# LB_BIT_i19_ROLLERSWITCH-v03_rev3.net
KiCad netlist of a schematic drawn in EAGLE
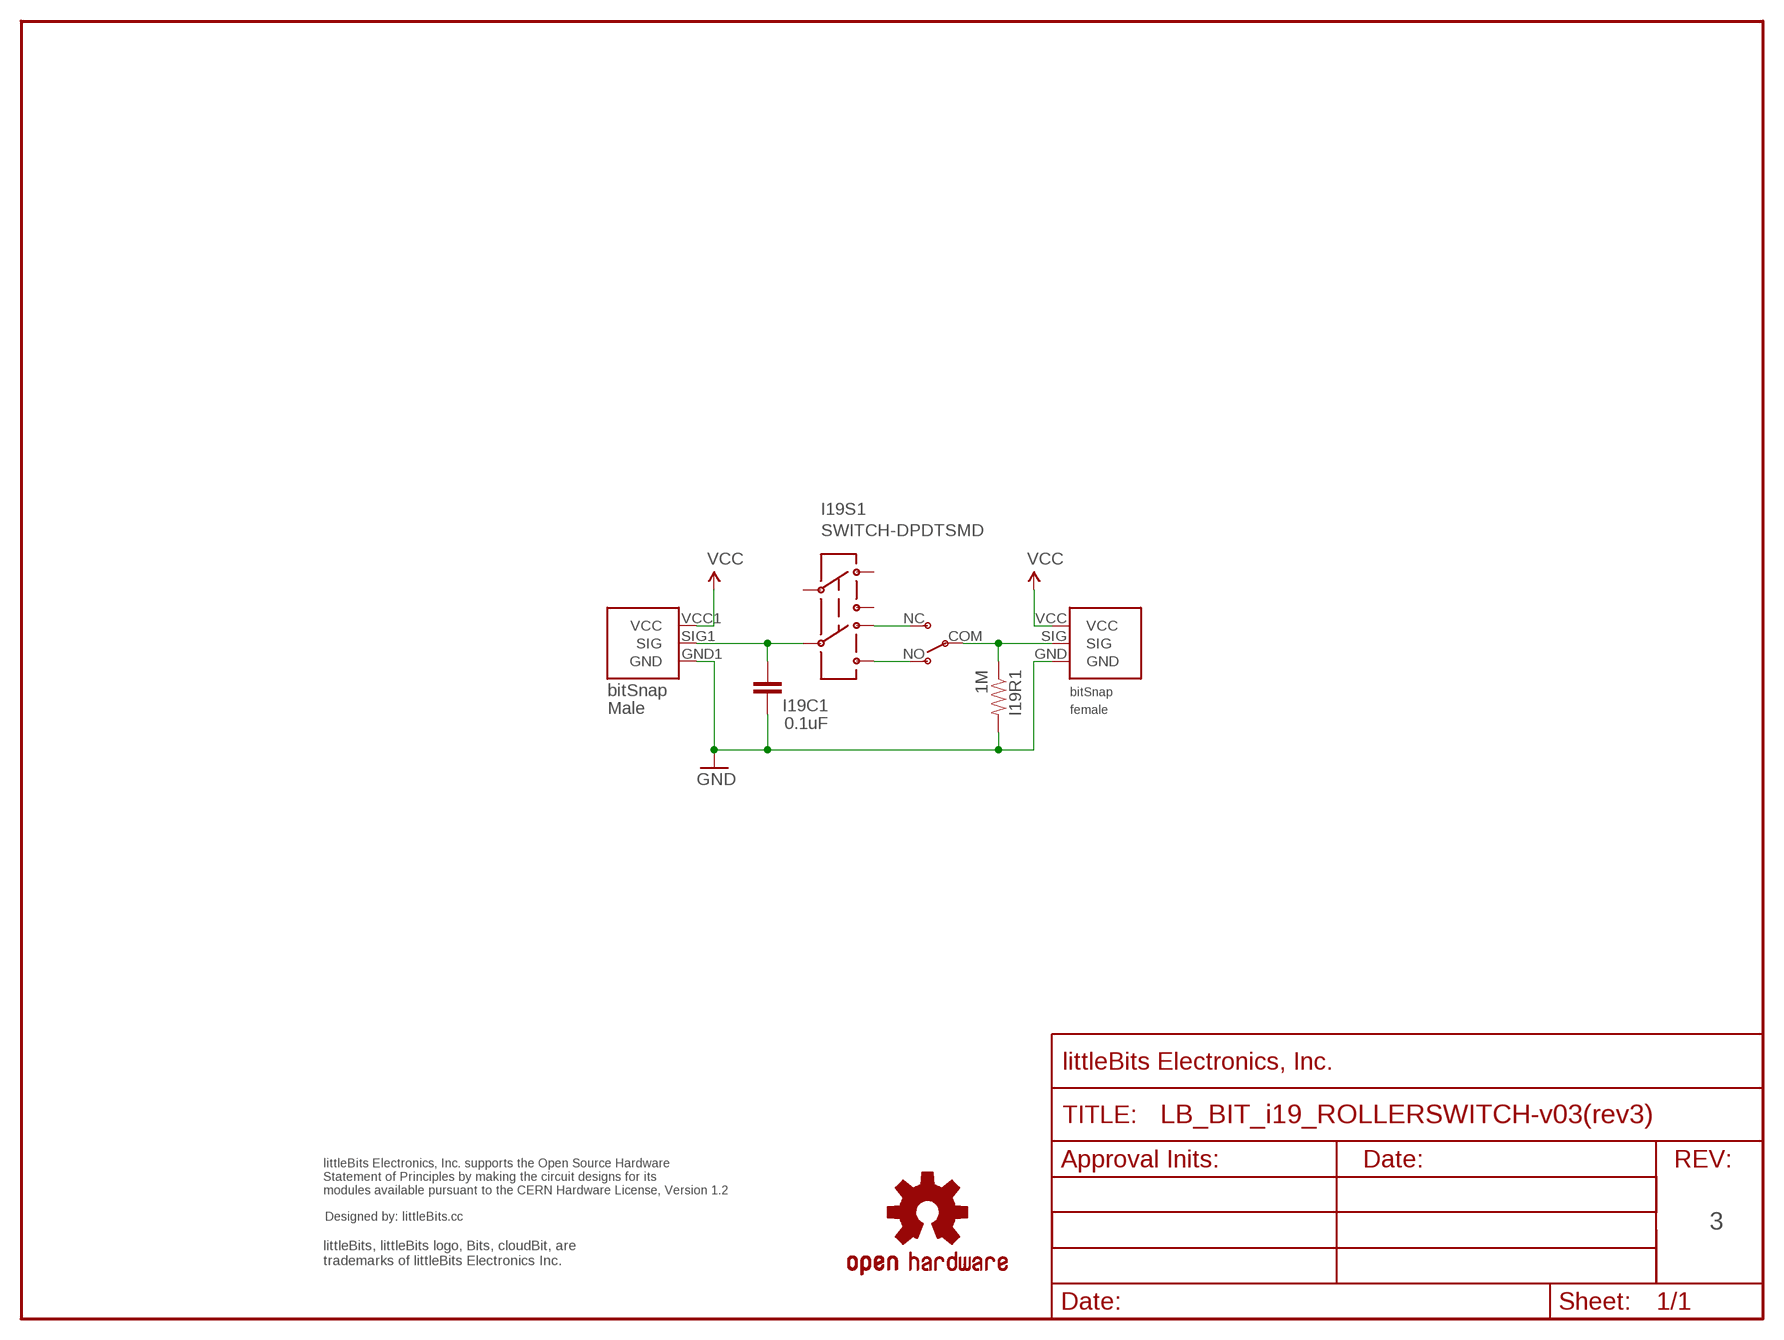
[diagram p0: schematic, sheet 1]

(export (version "E")
  (design (tool "Eeschema 10.0.6"))
  (components
    (comp (ref "FRAME1")
      (value "FRAME-LETTER-OHWOHW")
      (footprint "eagle-import:FABDWG01-OHW")
      (libsource (lib "eagle-import") (part "FRAME-LETTER-OHWOHW"))
    )
    (comp (ref "I19BSF1")
      (value "BITSNAP_V03_FEMALE")
      (footprint "eagle-import:BITSNAP_V03_FEMALE")
      (libsource (lib "eagle-import") (part "BITSNAP_V03_FEMALE"))
    )
    (comp (ref "I19BSM1")
      (value "BITSNAP_V03_MALE")
      (footprint "eagle-import:BITSNAP_V03_MALE")
      (libsource (lib "eagle-import") (part "BITSNAP_V03_MALE"))
    )
    (comp (ref "I19C1")
      (value "0.1uF")
      (footprint "eagle-import:0603-CAP")
      (libsource (lib "eagle-import") (part "CAP0603-CAP"))
    )
    (comp (ref "I19R1")
      (value "1M")
      (footprint "eagle-import:0603-RES")
      (libsource (lib "eagle-import") (part "RESISTOR0603-RES"))
    )
    (comp (ref "I19S1")
      (value "SWITCH-DPDTSMD")
      (footprint "eagle-import:AYZ0202")
      (libsource (lib "eagle-import") (part "SWITCH-DPDTSMD"))
    )
    (comp (ref "I19SW2")
      (value "ROLLERSWITCH-OMRON-SS-5GL2DRIGHTANGLE")
      (footprint "eagle-import:ROLLERSWITCH-OMRON-D2F-01FL-A")
      (libsource (lib "eagle-import") (part "ROLLERSWITCH-OMRON-SS-5GL2DRIGHTANGLE"))
    )
    (comp (ref "U$1")
      (value "OSHWCREDIT")
      (footprint "eagle-import:OSHWCREDIT")
      (libsource (lib "eagle-import") (part "OSHWCREDIT"))
    )
    (comp (ref "U$3")
      (value "OSHW-LOGOL")
      (footprint "eagle-import:OSHW-LOGO-L")
      (libsource (lib "eagle-import") (part "OSHW-LOGOL"))
    )
  )
  (nets
    (net (code "1") (name "GND") (class "Default")
      (node (ref "I19BSF1") (pin "GND") (pinfunction "GND_GND") (pintype "bidirectional"))
      (node (ref "I19BSM1") (pin "GND1") (pinfunction "GND_GND1") (pintype "bidirectional"))
      (node (ref "I19C1") (pin "1") (pinfunction "1_1") (pintype "passive"))
      (node (ref "I19R1") (pin "2") (pinfunction "2_2") (pintype "passive"))
    )
    (net (code "2") (name "Net-(I19BSF1-PadSIG)") (class "Default")
      (node (ref "I19BSF1") (pin "SIG") (pinfunction "SIG_SIG") (pintype "bidirectional"))
      (node (ref "I19R1") (pin "1") (pinfunction "1_1") (pintype "passive"))
      (node (ref "I19SW2") (pin "COM") (pinfunction "COM_COM") (pintype "passive"))
    )
    (net (code "3") (name "Net-(I19BSM1-SIG)") (class "Default")
      (node (ref "I19BSM1") (pin "SIG1") (pinfunction "SIG_SIG1") (pintype "bidirectional"))
      (node (ref "I19C1") (pin "2") (pinfunction "2_2") (pintype "passive"))
      (node (ref "I19S1") (pin "5") (pinfunction "5_5") (pintype "bidirectional"))
    )
    (net (code "4") (name "Net-(I19S1-Pad4)") (class "Default")
      (node (ref "I19S1") (pin "4") (pinfunction "4_4") (pintype "bidirectional"))
      (node (ref "I19SW2") (pin "NC") (pinfunction "NC_NC") (pintype "passive"))
    )
    (net (code "5") (name "Net-(I19S1-Pad6)") (class "Default")
      (node (ref "I19S1") (pin "6") (pinfunction "6_6") (pintype "bidirectional"))
      (node (ref "I19SW2") (pin "NO") (pinfunction "NO_NO") (pintype "passive"))
    )
    (net (code "6") (name "VCC") (class "Default")
      (node (ref "I19BSF1") (pin "VCC") (pinfunction "VCC_VCC") (pintype "bidirectional"))
      (node (ref "I19BSM1") (pin "VCC1") (pinfunction "VCC_VCC1") (pintype "bidirectional"))
    )
    (net (code "7") (name "unconnected-(I19S1-Pad1)") (class "Default")
      (node (ref "I19S1") (pin "1") (pinfunction "1_1") (pintype "bidirectional"))
    )
    (net (code "8") (name "unconnected-(I19S1-Pad2)") (class "Default")
      (node (ref "I19S1") (pin "2") (pinfunction "2_2") (pintype "bidirectional"))
    )
    (net (code "9") (name "unconnected-(I19S1-Pad3)") (class "Default")
      (node (ref "I19S1") (pin "3") (pinfunction "3_3") (pintype "bidirectional"))
    )
  )
)
